# Power.net
KiCad netlist of a schematic drawn in Altium Designer
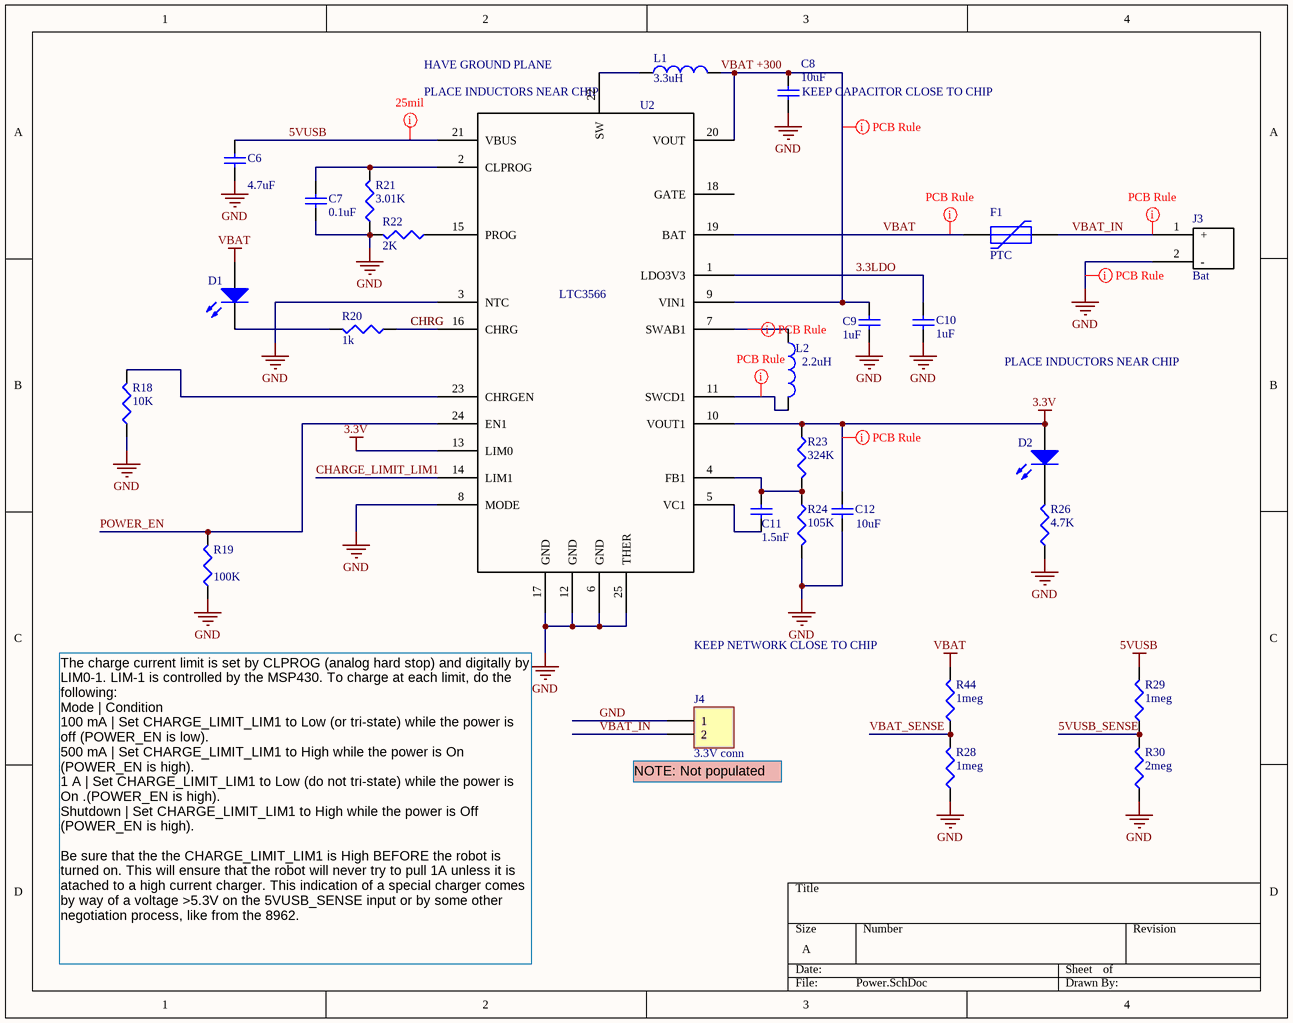
[diagram p0: Power.SchDoc]

(export (version "E")
  (design (tool "Eeschema 10.0.6"))
  (components
    (comp (ref "C6")
      (value "4.7uF")
      (footprint "CAPC1608L")
      (description "Capacitor (Semiconductor SIM Model)")
      (fields (field (name "Comment") "Cap Semi") (field (name "PUBLISHER") "Altium Limited"))
      (libsource (lib "Miscellaneous Devices") (part "Cap Semi"))
    )
    (comp (ref "C7")
      (value "0.1uF")
      (footprint "CAPC1005L")
      (description "Capacitor")
      (fields (field (name "Comment") "Cap") (field (name "PUBLISHER") "Altium Limited"))
      (libsource (lib "Miscellaneous Devices") (part "Cap"))
    )
    (comp (ref "C8")
      (value "10uF")
      (footprint "CAPC1608L")
      (description "Capacitor")
      (fields (field (name "Comment") "Cap") (field (name "PUBLISHER") "Altium Limited"))
      (libsource (lib "Miscellaneous Devices") (part "Cap"))
    )
    (comp (ref "C9")
      (value "1uF")
      (footprint "CAPC1608L")
      (description "Capacitor")
      (fields (field (name "Comment") "Cap") (field (name "PUBLISHER") "Altium Limited"))
      (libsource (lib "Miscellaneous Devices") (part "Cap"))
    )
    (comp (ref "C10")
      (value "1uF")
      (footprint "CAPC1608L")
      (description "Capacitor")
      (fields (field (name "Comment") "Cap") (field (name "PUBLISHER") "Altium Limited"))
      (libsource (lib "Miscellaneous Devices") (part "Cap"))
    )
    (comp (ref "C11")
      (value "1.5nF")
      (footprint "CAPC1005L")
      (description "Capacitor")
      (fields (field (name "Comment") "Cap") (field (name "PUBLISHER") "Altium Limited"))
      (libsource (lib "Miscellaneous Devices") (part "Cap"))
    )
    (comp (ref "C12")
      (value "10uF")
      (footprint "CAPC1608L")
      (description "Capacitor")
      (fields (field (name "Comment") "Cap") (field (name "PUBLISHER") "Altium Limited"))
      (libsource (lib "Miscellaneous Devices") (part "Cap"))
    )
    (comp (ref "D1")
      (value "Charge")
      (footprint "INDC2012L")
      (description "Typical RED, GREEN, YELLOW, AMBER GaAs LED")
      (fields (field (name "PUBLISHER") "Altium Limited"))
      (libsource (lib "Miscellaneous Devices") (part "LED2"))
    )
    (comp (ref "D2")
      (value "Power")
      (footprint "INDC2012L")
      (description "Typical RED, GREEN, YELLOW, AMBER GaAs LED")
      (fields (field (name "PUBLISHER") "Altium Limited"))
      (libsource (lib "Miscellaneous Devices") (part "LED2"))
    )
    (comp (ref "F1")
      (value "PTC")
      (footprint "ERJ8G-1206")
      (description "Fuse")
      (fields (field (name "PUBLISHER") "Altium Limited"))
      (libsource (lib "mrone") (part "PTC_FUSE"))
    )
    (comp (ref "J3")
      (value "Bat")
      (footprint "BatteryConnJST")
      (libsource (lib "mrone") (part "BatteryConnJST"))
    )
    (comp (ref "J4")
      (value "3.3V conn")
      (footprint "HDR1X2")
      (description "Header, 2-Pin")
      (fields (field (name "PUBLISHER") "Altium Limited"))
      (libsource (lib "Miscellaneous Connectors") (part "Header 2"))
    )
    (comp (ref "L1") (value "3.3uH") (footprint "IndPow") (libsource (lib "mrone") (part "Inductor")))
    (comp (ref "L2") (value "2.2uH") (footprint "IndPow") (libsource (lib "mrone") (part "Inductor")))
    (comp (ref "R18")
      (value "10K")
      (footprint "RESC1608L")
      (description "Resistor")
      (fields (field (name "Comment") "Res3") (field (name "PUBLISHER") "Altium Limited"))
      (libsource (lib "Miscellaneous Devices") (part "Res3"))
    )
    (comp (ref "R19")
      (value "100K")
      (footprint "RESC1608L")
      (description "Resistor")
      (fields (field (name "Comment") "Res3") (field (name "PUBLISHER") "Altium Limited"))
      (libsource (lib "Miscellaneous Devices") (part "Res3"))
    )
    (comp (ref "R20")
      (value "1k")
      (footprint "RESC1608L")
      (description "Resistor")
      (fields (field (name "Comment") "Res3") (field (name "PUBLISHER") "Altium Limited"))
      (libsource (lib "Miscellaneous Devices") (part "Res3"))
    )
    (comp (ref "R21")
      (value "3.01K")
      (footprint "RESC1608L")
      (description "Resistor")
      (fields (field (name "Comment") "Res3") (field (name "PUBLISHER") "Altium Limited"))
      (libsource (lib "Miscellaneous Devices") (part "Res3"))
    )
    (comp (ref "R22")
      (value "2K")
      (footprint "RESC1608L")
      (description "Resistor")
      (fields (field (name "Comment") "Res3") (field (name "PUBLISHER") "Altium Limited"))
      (libsource (lib "Miscellaneous Devices") (part "Res3"))
    )
    (comp (ref "R23")
      (value "324K")
      (footprint "RESC1608L")
      (description "Resistor")
      (fields (field (name "Comment") "Res3") (field (name "PUBLISHER") "Altium Limited"))
      (libsource (lib "Miscellaneous Devices") (part "Res3"))
    )
    (comp (ref "R24")
      (value "105K")
      (footprint "RESC1608L")
      (description "Resistor")
      (fields (field (name "Comment") "Res3") (field (name "PUBLISHER") "Altium Limited"))
      (libsource (lib "Miscellaneous Devices") (part "Res3"))
    )
    (comp (ref "R26")
      (value "4.7K")
      (footprint "RESC1608L")
      (description "Resistor")
      (fields (field (name "Comment") "Res3") (field (name "PUBLISHER") "Altium Limited"))
      (libsource (lib "Miscellaneous Devices") (part "Res3"))
    )
    (comp (ref "R28")
      (value "1meg")
      (footprint "RESC1608L")
      (description "Resistor")
      (fields (field (name "Comment") "Res3") (field (name "PUBLISHER") "Altium Limited"))
      (libsource (lib "Miscellaneous Devices") (part "Res3"))
    )
    (comp (ref "R29")
      (value "1meg")
      (footprint "RESC1608L")
      (description "Resistor")
      (fields (field (name "Comment") "Res3") (field (name "PUBLISHER") "Altium Limited"))
      (libsource (lib "Miscellaneous Devices") (part "Res3"))
    )
    (comp (ref "R30")
      (value "2meg")
      (footprint "RESC1608L")
      (description "Resistor")
      (fields (field (name "Comment") "Res3") (field (name "PUBLISHER") "Altium Limited"))
      (libsource (lib "Miscellaneous Devices") (part "Res3"))
    )
    (comp (ref "R44")
      (value "1meg")
      (footprint "RESC1608L")
      (description "Resistor")
      (fields (field (name "Comment") "Res3") (field (name "PUBLISHER") "Altium Limited"))
      (libsource (lib "Miscellaneous Devices") (part "Res3"))
    )
    (comp (ref "U2")
      (value "LTC3566")
      (footprint "QFN-24")
      (libsource (lib "Schematic Components") (part "LTC3566"))
    )
  )
  (nets
    (net (code "1") (name "/3.3LDO") (class "Default")
      (node (ref "C10") (pin "1") (pinfunction "1_1") (pintype "passive"))
      (node (ref "U2") (pin "1") (pinfunction "LDO3V3_1") (pintype "passive"))
    )
    (net (code "2") (name "/5VUSB_SENSE") (class "Default")
      (node (ref "R29") (pin "1") (pinfunction "1_1") (pintype "passive"))
      (node (ref "R30") (pin "2") (pinfunction "2_2") (pintype "passive"))
    )
    (net (code "3") (name "/CHARGE_LIMIT_LIM1") (class "Default")
      (node (ref "U2") (pin "14") (pinfunction "LIM1_14") (pintype "passive"))
    )
    (net (code "4") (name "/CHRG") (class "Default")
      (node (ref "R20") (pin "1") (pinfunction "1_1") (pintype "passive"))
      (node (ref "U2") (pin "16") (pinfunction "CHRG_16") (pintype "passive"))
    )
    (net (code "5") (name "/POWER_EN") (class "Default")
      (node (ref "R19") (pin "2") (pinfunction "2_2") (pintype "passive"))
      (node (ref "U2") (pin "24") (pinfunction "EN1_24") (pintype "passive"))
    )
    (net (code "6") (name "/VBAT +300") (class "Default")
      (node (ref "C8") (pin "2") (pinfunction "2_2") (pintype "passive"))
      (node (ref "C9") (pin "1") (pinfunction "1_1") (pintype "passive"))
      (node (ref "L1") (pin "2") (pinfunction "2_2") (pintype "passive"))
      (node (ref "U2") (pin "20") (pinfunction "VOUT_20") (pintype "passive"))
      (node (ref "U2") (pin "9") (pinfunction "VIN1_9") (pintype "passive"))
    )
    (net (code "7") (name "/VBAT_IN") (class "Default")
      (node (ref "F1") (pin "2") (pinfunction "2_2") (pintype "passive"))
      (node (ref "J3") (pin "1") (pinfunction "+_1") (pintype "passive"))
      (node (ref "J4") (pin "2") (pinfunction "2_2") (pintype "passive"))
    )
    (net (code "8") (name "/VBAT_SENSE") (class "Default")
      (node (ref "R28") (pin "2") (pinfunction "2_2") (pintype "passive"))
      (node (ref "R44") (pin "1") (pinfunction "1_1") (pintype "passive"))
    )
    (net (code "9") (name "3.3V") (class "Default")
      (node (ref "C12") (pin "2") (pinfunction "2_2") (pintype "passive"))
      (node (ref "D2") (pin "1") (pinfunction "A_1") (pintype "passive"))
      (node (ref "R23") (pin "1") (pinfunction "1_1") (pintype "passive"))
      (node (ref "U2") (pin "10") (pinfunction "VOUT1_10") (pintype "passive"))
      (node (ref "U2") (pin "13") (pinfunction "LIM0_13") (pintype "passive"))
    )
    (net (code "10") (name "5VUSB") (class "Default")
      (node (ref "C6") (pin "2") (pinfunction "2_2") (pintype "passive"))
      (node (ref "R29") (pin "2") (pinfunction "2_2") (pintype "passive"))
      (node (ref "U2") (pin "21") (pinfunction "VBUS_21") (pintype "passive"))
    )
    (net (code "11") (name "GND") (class "Default")
      (node (ref "C10") (pin "2") (pinfunction "2_2") (pintype "passive"))
      (node (ref "C12") (pin "1") (pinfunction "1_1") (pintype "passive"))
      (node (ref "C6") (pin "1") (pinfunction "1_1") (pintype "passive"))
      (node (ref "C7") (pin "1") (pinfunction "1_1") (pintype "passive"))
      (node (ref "C8") (pin "1") (pinfunction "1_1") (pintype "passive"))
      (node (ref "C9") (pin "2") (pinfunction "2_2") (pintype "passive"))
      (node (ref "J3") (pin "2") (pinfunction "-_2") (pintype "passive"))
      (node (ref "J4") (pin "1") (pinfunction "1_1") (pintype "passive"))
      (node (ref "R18") (pin "1") (pinfunction "1_1") (pintype "passive"))
      (node (ref "R19") (pin "1") (pinfunction "1_1") (pintype "passive"))
      (node (ref "R21") (pin "1") (pinfunction "1_1") (pintype "passive"))
      (node (ref "R22") (pin "2") (pinfunction "2_2") (pintype "passive"))
      (node (ref "R24") (pin "2") (pinfunction "2_2") (pintype "passive"))
      (node (ref "R26") (pin "1") (pinfunction "1_1") (pintype "passive"))
      (node (ref "R28") (pin "1") (pinfunction "1_1") (pintype "passive"))
      (node (ref "R30") (pin "1") (pinfunction "1_1") (pintype "passive"))
      (node (ref "U2") (pin "12") (pinfunction "GND_12") (pintype "passive"))
      (node (ref "U2") (pin "17") (pinfunction "GND_17") (pintype "passive"))
      (node (ref "U2") (pin "25") (pinfunction "THER_25") (pintype "passive"))
      (node (ref "U2") (pin "3") (pinfunction "NTC_3") (pintype "passive"))
      (node (ref "U2") (pin "6") (pinfunction "GND_6") (pintype "passive"))
      (node (ref "U2") (pin "8") (pinfunction "MODE_8") (pintype "passive"))
    )
    (net (code "12") (name "Net-(D1-K)") (class "Default")
      (node (ref "D1") (pin "2") (pinfunction "K_2") (pintype "passive"))
      (node (ref "R20") (pin "2") (pinfunction "2_2") (pintype "passive"))
    )
    (net (code "13") (name "Net-(D2-K)") (class "Default")
      (node (ref "D2") (pin "2") (pinfunction "K_2") (pintype "passive"))
      (node (ref "R26") (pin "2") (pinfunction "2_2") (pintype "passive"))
    )
    (net (code "14") (name "Net-(U2-CHRGEN)") (class "Default")
      (node (ref "R18") (pin "2") (pinfunction "2_2") (pintype "passive"))
      (node (ref "U2") (pin "23") (pinfunction "CHRGEN_23") (pintype "passive"))
    )
    (net (code "15") (name "Net-(U2-CLPROG)") (class "Default")
      (node (ref "C7") (pin "2") (pinfunction "2_2") (pintype "passive"))
      (node (ref "R21") (pin "2") (pinfunction "2_2") (pintype "passive"))
      (node (ref "U2") (pin "2") (pinfunction "CLPROG_2") (pintype "passive"))
    )
    (net (code "16") (name "Net-(U2-FB1)") (class "Default")
      (node (ref "C11") (pin "1") (pinfunction "1_1") (pintype "passive"))
      (node (ref "R23") (pin "2") (pinfunction "2_2") (pintype "passive"))
      (node (ref "R24") (pin "1") (pinfunction "1_1") (pintype "passive"))
      (node (ref "U2") (pin "4") (pinfunction "FB1_4") (pintype "passive"))
    )
    (net (code "17") (name "Net-(U2-PROG)") (class "Default")
      (node (ref "R22") (pin "1") (pinfunction "1_1") (pintype "passive"))
      (node (ref "U2") (pin "15") (pinfunction "PROG_15") (pintype "passive"))
    )
    (net (code "18") (name "Net-(U2-SW)") (class "Default")
      (node (ref "L1") (pin "1") (pinfunction "1_1") (pintype "passive"))
      (node (ref "U2") (pin "22") (pinfunction "SW_22") (pintype "passive"))
    )
    (net (code "19") (name "Net-(U2-SWAB1)") (class "Default")
      (node (ref "L2") (pin "1") (pinfunction "1_1") (pintype "passive"))
      (node (ref "U2") (pin "7") (pinfunction "SWAB1_7") (pintype "passive"))
    )
    (net (code "20") (name "Net-(U2-SWCD1)") (class "Default")
      (node (ref "L2") (pin "2") (pinfunction "2_2") (pintype "passive"))
      (node (ref "U2") (pin "11") (pinfunction "SWCD1_11") (pintype "passive"))
    )
    (net (code "21") (name "Net-(U2-VC1)") (class "Default")
      (node (ref "C11") (pin "2") (pinfunction "2_2") (pintype "passive"))
      (node (ref "U2") (pin "5") (pinfunction "VC1_5") (pintype "passive"))
    )
    (net (code "22") (name "VBAT") (class "Default")
      (node (ref "D1") (pin "1") (pinfunction "A_1") (pintype "passive"))
      (node (ref "F1") (pin "1") (pinfunction "1_1") (pintype "passive"))
      (node (ref "R44") (pin "2") (pinfunction "2_2") (pintype "passive"))
      (node (ref "U2") (pin "19") (pinfunction "BAT_19") (pintype "passive"))
    )
    (net (code "23") (name "unconnected-(U2-GATE-Pad18)") (class "Default")
      (node (ref "U2") (pin "18") (pinfunction "GATE_18") (pintype "passive"))
    )
  )
)
